# PowerAndInput.net
KiCad netlist of a schematic drawn in Altium Designer
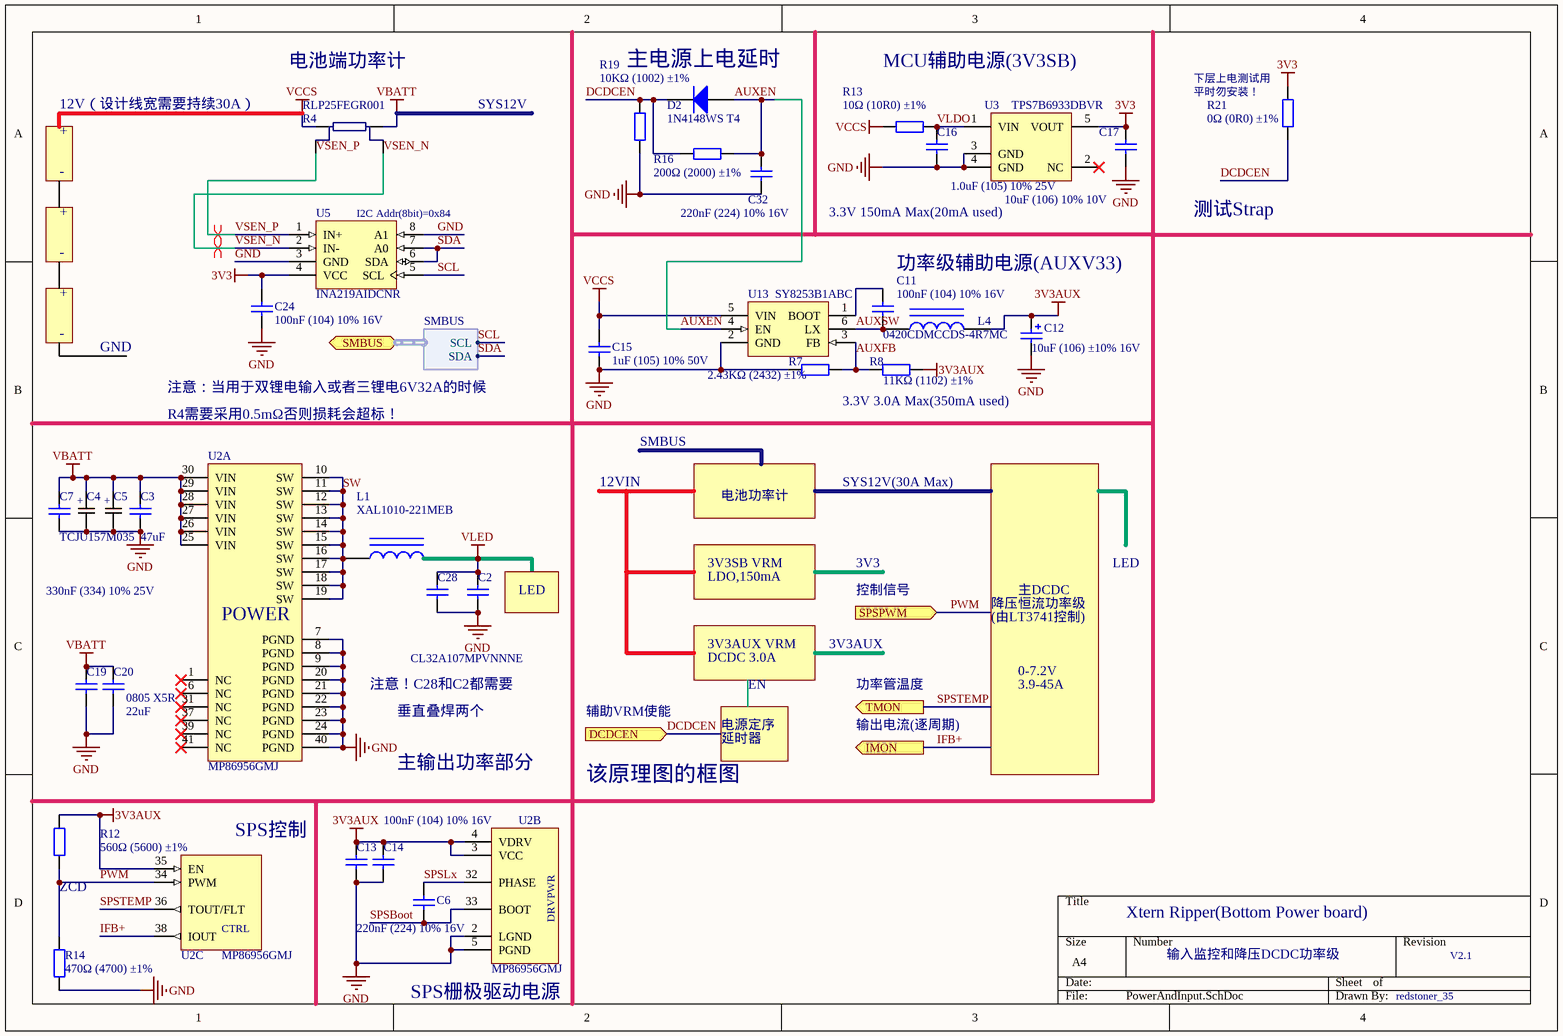
[diagram p0: PowerAndInput.SchDoc]

(export (version "E")
  (design (tool "Eeschema 10.0.6"))
  (components
    (comp (ref "C2")
      (value "CC1210KKX5RBB476")
      (footprint "1210C")
      (description "1210 MLCC X5R 16V 10%")
      (fields (field (name "PUBLISHER") "Altium Limited"))
      (libsource (lib "山猫的集成库20190318") (part "Cap"))
    )
    (comp (ref "C3")
      (value "47uF")
      (footprint "1210C")
      (description "1210 MLCC X5R 16V 10%")
      (fields (field (name "Comment") "CC1210KKX5RBB476") (field (name "PUBLISHER") "Altium Limited"))
      (libsource (lib "山猫的集成库20190318") (part "Cap"))
    )
    (comp (ref "C4")
      (value "TCJU157M035")
      (footprint "CAPMP7362X41N")
      (description "35V 150uF Conductive Polymer Solid Capacitor 100mR ESR. 7362 Size")
      (libsource (lib "custom") (part "TCJU157M035R0100E"))
    )
    (comp (ref "C5")
      (value "TCJU157M035")
      (footprint "CAPMP7362X41N")
      (description "35V 150uF Conductive Polymer Solid Capacitor 100mR ESR. 7362 Size")
      (libsource (lib "custom") (part "TCJU157M035R0100E"))
    )
    (comp (ref "C6")
      (value "220nF (224) 10% 16V")
      (footprint "0402_C")
      (description "贴片电容")
      (libsource (lib "Miscellaneous Devices LC") (part "0402 220nF (224) 10% 16V"))
    )
    (comp (ref "C7")
      (value "330nF (334) 10% 25V")
      (footprint "0603_C")
      (description "贴片电容")
      (libsource (lib "Miscellaneous Devices LC") (part "0603 330nF (334) 10% 25V"))
    )
    (comp (ref "C11")
      (value "100nF (104) 10% 16V")
      (footprint "0402_C")
      (description "贴片电容")
      (libsource (lib "Miscellaneous Devices LC") (part "0402 100nF (104) 10% 16V"))
    )
    (comp (ref "C12")
      (value "10uF (106) ±10% 16V")
      (footprint "CASE-A_3216")
      (description "钽电容")
      (libsource (lib "Miscellaneous Devices LC") (part "3216 10uF (106) 10% 16V"))
    )
    (comp (ref "C13")
      (value "100nF (104) 10% 16V")
      (footprint "0402_C")
      (description "贴片电容")
      (libsource (lib "Miscellaneous Devices LC") (part "0402 100nF (104) 10% 16V"))
    )
    (comp (ref "C14")
      (value "100nF (104) 10% 16V")
      (footprint "0402_C")
      (description "贴片电容")
      (libsource (lib "Miscellaneous Devices LC") (part "0402 100nF (104) 10% 16V"))
    )
    (comp (ref "C15")
      (value "1uF (105) 10% 50V")
      (footprint "0603_C")
      (description "贴片电容")
      (libsource (lib "Miscellaneous Devices LC") (part "0603 1uF (105) 10% 50V"))
    )
    (comp (ref "C16")
      (value "1.0uF (105) 10% 25V")
      (footprint "0402_C")
      (description "贴片电容")
      (libsource (lib "Miscellaneous Devices LC") (part "0402 1.0uF (105) 10% 25V"))
    )
    (comp (ref "C17")
      (value "10uF (106) 10% 10V")
      (footprint "0603_C")
      (description "贴片电容")
      (libsource (lib "Miscellaneous Devices LC") (part "0603 10uF (106) 10% 10V"))
    )
    (comp (ref "C19")
      (value "0805 X5R")
      (footprint "0805C")
      (description "Capacitor")
      (fields (field (name "PUBLISHER") "Altium Limited"))
      (libsource (lib "山猫的集成库20190318") (part "Cap"))
    )
    (comp (ref "C20")
      (value "0805 X5R")
      (footprint "0805C")
      (description "Capacitor")
      (fields (field (name "ALTIUM_VALUE") "22uF") (field (name "PUBLISHER") "Altium Limited"))
      (libsource (lib "山猫的集成库20190318") (part "Cap"))
    )
    (comp (ref "C24")
      (value "100nF (104) 10% 16V")
      (footprint "0402_C")
      (description "贴片电容")
      (libsource (lib "Miscellaneous Devices LC") (part "0402 100nF (104) 10% 16V"))
    )
    (comp (ref "C28")
      (value "CL32A107MPVNNNE")
      (footprint "1210C")
      (description "1210 MLCC X5R 16V 10%")
      (fields (field (name "PUBLISHER") "Altium Limited"))
      (libsource (lib "山猫的集成库20190318") (part "Cap"))
    )
    (comp (ref "C32")
      (value "220nF (224) 10% 16V")
      (footprint "0402_C")
      (description "贴片电容")
      (libsource (lib "Miscellaneous Devices LC") (part "0402 220nF (224) 10% 16V"))
    )
    (comp (ref "D2")
      (value "1N4148WS T4")
      (footprint "SOD-323")
      (description "二极管")
      (libsource (lib "Miscellaneous Devices LC") (part "SOD-323 1N4148WS T4"))
    )
    (comp (ref "L1")
      (value "XAL1010-221MEB")
      (footprint "XAL1010-XXXME")
      (description "Coilcraft Inductor XAL1010 Series")
      (fields (field (name "PUBLISHER") "Altium Limited"))
      (libsource (lib "Miscellaneous Devices") (part "Inductor Iron"))
    )
    (comp (ref "L4")
      (value "0420CDMCCDS-4R7MC")
      (footprint "0420CDMCCDS-***MC")
      (description "Magnetic-Core Inductor")
      (fields (field (name "PUBLISHER") "Altium Limited"))
      (libsource (lib "Miscellaneous Devices") (part "Inductor Iron"))
    )
    (comp (ref "R4")
      (value "RLP25FEGR001")
      (footprint "2512-Virtual4Wire")
      (description "2512 1mΩ合金检流电阻 3W")
      (libsource (lib "custom") (part "shunt"))
    )
    (comp (ref "R7")
      (value "2.43KΩ (2432) ±1%")
      (footprint "0402_R")
      (description "贴片电阻")
      (libsource (lib "") (part "0402 0Ω (0R0) 1%_1"))
    )
    (comp (ref "R8")
      (value "11KΩ (1102) ±1%")
      (footprint "0402_R")
      (description "贴片电阻")
      (libsource (lib "") (part "0402 0Ω (0R0) 1%_1"))
    )
    (comp (ref "R12")
      (value "560Ω (5600) ±1%")
      (footprint "0402_R")
      (description "贴片电阻")
      (libsource (lib "Miscellaneous Devices LC") (part "0402 22KΩ (2202) 1%"))
    )
    (comp (ref "R13")
      (value "10Ω (10R0) ±1%")
      (footprint "0402_R")
      (description "贴片电阻")
      (libsource (lib "Miscellaneous Devices LC") (part "0402 10Ω (10R0) 1%"))
    )
    (comp (ref "R14")
      (value "470Ω (4700) ±1%")
      (footprint "0402_R")
      (description "贴片电阻")
      (libsource (lib "Miscellaneous Devices LC") (part "0402 470Ω (4700) 1%"))
    )
    (comp (ref "R16")
      (value "200Ω (2000) ±1%")
      (footprint "0402_R")
      (description "贴片电阻")
      (libsource (lib "Miscellaneous Devices LC") (part "0402 200Ω (2000) 1%"))
    )
    (comp (ref "R19")
      (value "10KΩ (1002) ±1%")
      (footprint "0402_R")
      (description "贴片电阻")
      (libsource (lib "Miscellaneous Devices LC") (part "0402 10KΩ (1002) 1%"))
    )
    (comp (ref "R21")
      (value "0Ω (0R0) ±1%")
      (footprint "0402_R")
      (description "贴片电阻")
      (libsource (lib "Miscellaneous Devices LC") (part "0402 0Ω (0R0) 1%"))
    )
    (comp (ref "U2")
      (value "MP86956GMJ")
      (footprint "TDA21490")
      (description "MPS 70A INTELLI-PHASE SPS in 5x6mm QFN41")
      (libsource (lib "custom") (part "MP86957"))
    )
    (comp (ref "U3")
      (value "TPS7B6933DBVR")
      (footprint "SOT95P245X110-5N")
      (description "150mA 40V max input Ultra low Iq LDO,fixed 3.3V output")
      (libsource (lib "custom") (part "TPS7B6933DBVR"))
    )
    (comp (ref "U5")
      (value "INA219AIDCNR")
      (footprint "SOT23-8")
      (description "26V Dual Direction 12bit I2C Power Gauge SOT23-8")
      (libsource (lib "custom") (part "INA219AIDCNR"))
    )
    (comp (ref "U13")
      (value "SY8253B1ABC")
      (footprint "SOT95P245X110-6N")
      (description "3A 23V Input 500KHz Sync step down converter")
      (libsource (lib "custom") (part "SY8120"))
    )
  )
  (nets
    (net (code "2") (name "/AUXEN") (class "Default")
      (node (ref "C32") (pin "1") (pinfunction "1_1") (pintype "passive"))
      (node (ref "D2") (pin "1") (pinfunction "A_1") (pintype "passive"))
      (node (ref "R16") (pin "2") (pinfunction "2_2") (pintype "passive"))
      (node (ref "U13") (pin "4") (pinfunction "EN_4") (pintype "input"))
    )
    (net (code "3") (name "/AUXFB") (class "Default")
      (node (ref "R7") (pin "2") (pinfunction "2_2") (pintype "passive"))
      (node (ref "R8") (pin "1") (pinfunction "1_1") (pintype "passive"))
      (node (ref "U13") (pin "3") (pinfunction "FB_3") (pintype "input"))
    )
    (net (code "4") (name "/AUXSW") (class "Default")
      (node (ref "C11") (pin "1") (pinfunction "1_1") (pintype "passive"))
      (node (ref "L4") (pin "1") (pinfunction "1_1") (pintype "passive"))
      (node (ref "U13") (pin "6") (pinfunction "LX_6") (pintype "power_in"))
    )
    (net (code "5") (name "/DCDCEN") (class "Default")
      (node (ref "D2") (pin "2") (pinfunction "K_2") (pintype "passive"))
      (node (ref "R16") (pin "1") (pinfunction "1_1") (pintype "passive"))
      (node (ref "R19") (pin "2") (pinfunction "2_2") (pintype "passive"))
      (node (ref "R21") (pin "1") (pinfunction "1_1") (pintype "passive"))
    )
    (net (code "6") (name "/IFB+") (class "Default")
      (node (ref "U2") (pin "38") (pinfunction "IOUT_38") (pintype "output"))
    )
    (net (code "7") (name "/PWM") (class "Default")
      (node (ref "R12") (pin "1") (pinfunction "1_1") (pintype "passive"))
      (node (ref "R14") (pin "2") (pinfunction "2_2") (pintype "passive"))
      (node (ref "U2") (pin "34") (pinfunction "PWM_34") (pintype "input"))
    )
    (net (code "8") (name "/SCL") (class "Default")
      (node (ref "U5") (pin "5") (pinfunction "SCL_5") (pintype "input"))
    )
    (net (code "9") (name "/SDA") (class "Default")
      (node (ref "U5") (pin "6") (pinfunction "SDA_6") (pintype "bidirectional"))
      (node (ref "U5") (pin "7") (pinfunction "A0_7") (pintype "input"))
    )
    (net (code "10") (name "/SPSBoot") (class "Default")
      (node (ref "C6") (pin "1") (pinfunction "1_1") (pintype "passive"))
      (node (ref "U2") (pin "33") (pinfunction "BOOT_33") (pintype "power_in"))
    )
    (net (code "11") (name "/SPSLx") (class "Default")
      (node (ref "C6") (pin "2") (pinfunction "2_2") (pintype "passive"))
      (node (ref "U2") (pin "32") (pinfunction "PHASE_32") (pintype "power_in"))
    )
    (net (code "12") (name "/SPSTEMP") (class "Default")
      (node (ref "U2") (pin "36") (pinfunction "TOUT/FLT_36") (pintype "output"))
    )
    (net (code "13") (name "/SW") (class "Default")
      (node (ref "L1") (pin "1") (pinfunction "1_1") (pintype "passive"))
      (node (ref "U2") (pin "10") (pinfunction "SW_10") (pintype "power_in"))
      (node (ref "U2") (pin "11") (pinfunction "SW_11") (pintype "power_in"))
      (node (ref "U2") (pin "12") (pinfunction "SW_12") (pintype "power_in"))
      (node (ref "U2") (pin "13") (pinfunction "SW_13") (pintype "power_in"))
      (node (ref "U2") (pin "14") (pinfunction "SW_14") (pintype "power_in"))
      (node (ref "U2") (pin "15") (pinfunction "SW_15") (pintype "power_in"))
      (node (ref "U2") (pin "16") (pinfunction "SW_16") (pintype "power_in"))
      (node (ref "U2") (pin "17") (pinfunction "SW_17") (pintype "power_in"))
      (node (ref "U2") (pin "18") (pinfunction "SW_18") (pintype "power_in"))
      (node (ref "U2") (pin "19") (pinfunction "SW_19") (pintype "power_in"))
    )
    (net (code "14") (name "/VLDO") (class "Default")
      (node (ref "C16") (pin "2") (pinfunction "2_2") (pintype "passive"))
      (node (ref "R13") (pin "2") (pinfunction "2_2") (pintype "passive"))
      (node (ref "U3") (pin "1") (pinfunction "VIN_1") (pintype "power_in"))
    )
    (net (code "15") (name "/VSEN_N") (class "Default")
      (node (ref "R4") (pin "2") (pinfunction "CIN_2") (pintype "passive"))
      (node (ref "U5") (pin "2") (pinfunction "IN-_2") (pintype "input"))
    )
    (net (code "16") (name "/VSEN_P") (class "Default")
      (node (ref "R4") (pin "3") (pinfunction "CIN_3") (pintype "passive"))
      (node (ref "U5") (pin "1") (pinfunction "IN+_1") (pintype "input"))
    )
    (net (code "18") (name "3V3") (class "Default")
      (node (ref "C17") (pin "2") (pinfunction "2_2") (pintype "passive"))
      (node (ref "C24") (pin "2") (pinfunction "2_2") (pintype "passive"))
      (node (ref "R21") (pin "2") (pinfunction "2_2") (pintype "passive"))
      (node (ref "U3") (pin "5") (pinfunction "VOUT_5") (pintype "power_in"))
      (node (ref "U5") (pin "4") (pinfunction "VCC_4") (pintype "power_in"))
    )
    (net (code "19") (name "3V3AUX") (class "Default")
      (node (ref "C12") (pin "1") (pinfunction "1_1") (pintype "passive"))
      (node (ref "C13") (pin "2") (pinfunction "2_2") (pintype "passive"))
      (node (ref "C14") (pin "2") (pinfunction "2_2") (pintype "passive"))
      (node (ref "L4") (pin "2") (pinfunction "2_2") (pintype "passive"))
      (node (ref "R12") (pin "2") (pinfunction "2_2") (pintype "passive"))
      (node (ref "R8") (pin "2") (pinfunction "2_2") (pintype "passive"))
      (node (ref "U2") (pin "3") (pinfunction "VCC_3") (pintype "power_in"))
      (node (ref "U2") (pin "35") (pinfunction "EN_35") (pintype "input"))
      (node (ref "U2") (pin "4") (pinfunction "VDRV_4") (pintype "power_in"))
    )
    (net (code "20") (name "GND") (class "Default")
      (node (ref "C12") (pin "2") (pinfunction "2_2") (pintype "passive"))
      (node (ref "C13") (pin "1") (pinfunction "1_1") (pintype "passive"))
      (node (ref "C14") (pin "1") (pinfunction "1_1") (pintype "passive"))
      (node (ref "C15") (pin "1") (pinfunction "1_1") (pintype "passive"))
      (node (ref "C16") (pin "1") (pinfunction "1_1") (pintype "passive"))
      (node (ref "C17") (pin "1") (pinfunction "1_1") (pintype "passive"))
      (node (ref "C19") (pin "1") (pinfunction "1_1") (pintype "passive"))
      (node (ref "C2") (pin "1") (pinfunction "1_1") (pintype "passive"))
      (node (ref "C20") (pin "1") (pinfunction "1_1") (pintype "passive"))
      (node (ref "C24") (pin "1") (pinfunction "1_1") (pintype "passive"))
      (node (ref "C28") (pin "1") (pinfunction "1_1") (pintype "passive"))
      (node (ref "C3") (pin "1") (pinfunction "1_1") (pintype "passive"))
      (node (ref "C32") (pin "2") (pinfunction "2_2") (pintype "passive"))
      (node (ref "C4") (pin "2") (pinfunction "-_2") (pintype "passive"))
      (node (ref "C5") (pin "2") (pinfunction "-_2") (pintype "passive"))
      (node (ref "C7") (pin "1") (pinfunction "1_1") (pintype "passive"))
      (node (ref "R14") (pin "1") (pinfunction "1_1") (pintype "passive"))
      (node (ref "R19") (pin "1") (pinfunction "1_1") (pintype "passive"))
      (node (ref "R7") (pin "1") (pinfunction "1_1") (pintype "passive"))
      (node (ref "U13") (pin "2") (pinfunction "GND_2") (pintype "passive"))
      (node (ref "U2") (pin "2") (pinfunction "LGND_2") (pintype "power_in"))
      (node (ref "U2") (pin "20") (pinfunction "PGND_20") (pintype "power_in"))
      (node (ref "U2") (pin "21") (pinfunction "PGND_21") (pintype "power_in"))
      (node (ref "U2") (pin "22") (pinfunction "PGND_22") (pintype "power_in"))
      (node (ref "U2") (pin "23") (pinfunction "PGND_23") (pintype "power_in"))
      (node (ref "U2") (pin "24") (pinfunction "PGND_24") (pintype "power_in"))
      (node (ref "U2") (pin "40") (pinfunction "PGND_40") (pintype "power_in"))
      (node (ref "U2") (pin "5") (pinfunction "PGND_5") (pintype "power_in"))
      (node (ref "U2") (pin "7") (pinfunction "PGND_7") (pintype "power_in"))
      (node (ref "U2") (pin "8") (pinfunction "PGND_8") (pintype "power_in"))
      (node (ref "U2") (pin "9") (pinfunction "PGND_9") (pintype "power_in"))
      (node (ref "U3") (pin "3") (pinfunction "GND_3") (pintype "power_in"))
      (node (ref "U3") (pin "4") (pinfunction "GND_4") (pintype "power_in"))
      (node (ref "U5") (pin "3") (pinfunction "GND_3") (pintype "power_in"))
      (node (ref "U5") (pin "8") (pinfunction "A1_8") (pintype "input"))
    )
    (net (code "21") (name "Net-(U13-BOOT)") (class "Default")
      (node (ref "C11") (pin "2") (pinfunction "2_2") (pintype "passive"))
      (node (ref "U13") (pin "1") (pinfunction "BOOT_1") (pintype "passive"))
    )
    (net (code "22") (name "VBATT") (class "Default")
      (node (ref "C19") (pin "2") (pinfunction "2_2") (pintype "passive"))
      (node (ref "C20") (pin "2") (pinfunction "2_2") (pintype "passive"))
      (node (ref "C3") (pin "2") (pinfunction "2_2") (pintype "passive"))
      (node (ref "C4") (pin "1") (pinfunction "+_1") (pintype "passive"))
      (node (ref "C5") (pin "1") (pinfunction "+_1") (pintype "passive"))
      (node (ref "C7") (pin "2") (pinfunction "2_2") (pintype "passive"))
      (node (ref "R4") (pin "0") (pinfunction "CIN_0") (pintype "passive"))
      (node (ref "U2") (pin "25") (pinfunction "VIN_25") (pintype "power_in"))
      (node (ref "U2") (pin "26") (pinfunction "VIN_26") (pintype "power_in"))
      (node (ref "U2") (pin "27") (pinfunction "VIN_27") (pintype "power_in"))
      (node (ref "U2") (pin "28") (pinfunction "VIN_28") (pintype "power_in"))
      (node (ref "U2") (pin "29") (pinfunction "VIN_29") (pintype "power_in"))
      (node (ref "U2") (pin "30") (pinfunction "VIN_30") (pintype "power_in"))
    )
    (net (code "23") (name "VCCS") (class "Default")
      (node (ref "C15") (pin "2") (pinfunction "2_2") (pintype "passive"))
      (node (ref "R13") (pin "1") (pinfunction "1_1") (pintype "passive"))
      (node (ref "R4") (pin "1") (pinfunction "CIN_1") (pintype "passive"))
      (node (ref "U13") (pin "5") (pinfunction "VIN_5") (pintype "power_in"))
    )
    (net (code "24") (name "VLED") (class "Default")
      (node (ref "C2") (pin "2") (pinfunction "2_2") (pintype "passive"))
      (node (ref "C28") (pin "2") (pinfunction "2_2") (pintype "passive"))
      (node (ref "L1") (pin "2") (pinfunction "2_2") (pintype "passive"))
    )
    (net (code "25") (name "unconnected-(U2A-NC-Pad1)") (class "Default")
      (node (ref "U2") (pin "1") (pinfunction "NC_1") (pintype "passive+no_connect"))
    )
    (net (code "26") (name "unconnected-(U2A-NC-Pad6)") (class "Default")
      (node (ref "U2") (pin "6") (pinfunction "NC_6") (pintype "passive+no_connect"))
    )
    (net (code "27") (name "unconnected-(U2A-NC-Pad31)") (class "Default")
      (node (ref "U2") (pin "31") (pinfunction "NC_31") (pintype "passive+no_connect"))
    )
    (net (code "28") (name "unconnected-(U2A-NC-Pad37)") (class "Default")
      (node (ref "U2") (pin "37") (pinfunction "NC_37") (pintype "passive+no_connect"))
    )
    (net (code "29") (name "unconnected-(U2A-NC-Pad39)") (class "Default")
      (node (ref "U2") (pin "39") (pinfunction "NC_39") (pintype "passive+no_connect"))
    )
    (net (code "30") (name "unconnected-(U2A-NC-Pad41)") (class "Default")
      (node (ref "U2") (pin "41") (pinfunction "NC_41") (pintype "passive+no_connect"))
    )
    (net (code "31") (name "unconnected-(U3-NC-Pad2)") (class "Default")
      (node (ref "U3") (pin "2") (pinfunction "NC_2") (pintype "passive+no_connect"))
    )
  )
)
